# XMEGAbreakoutTH.net
KiCad netlist of a schematic drawn in EAGLE
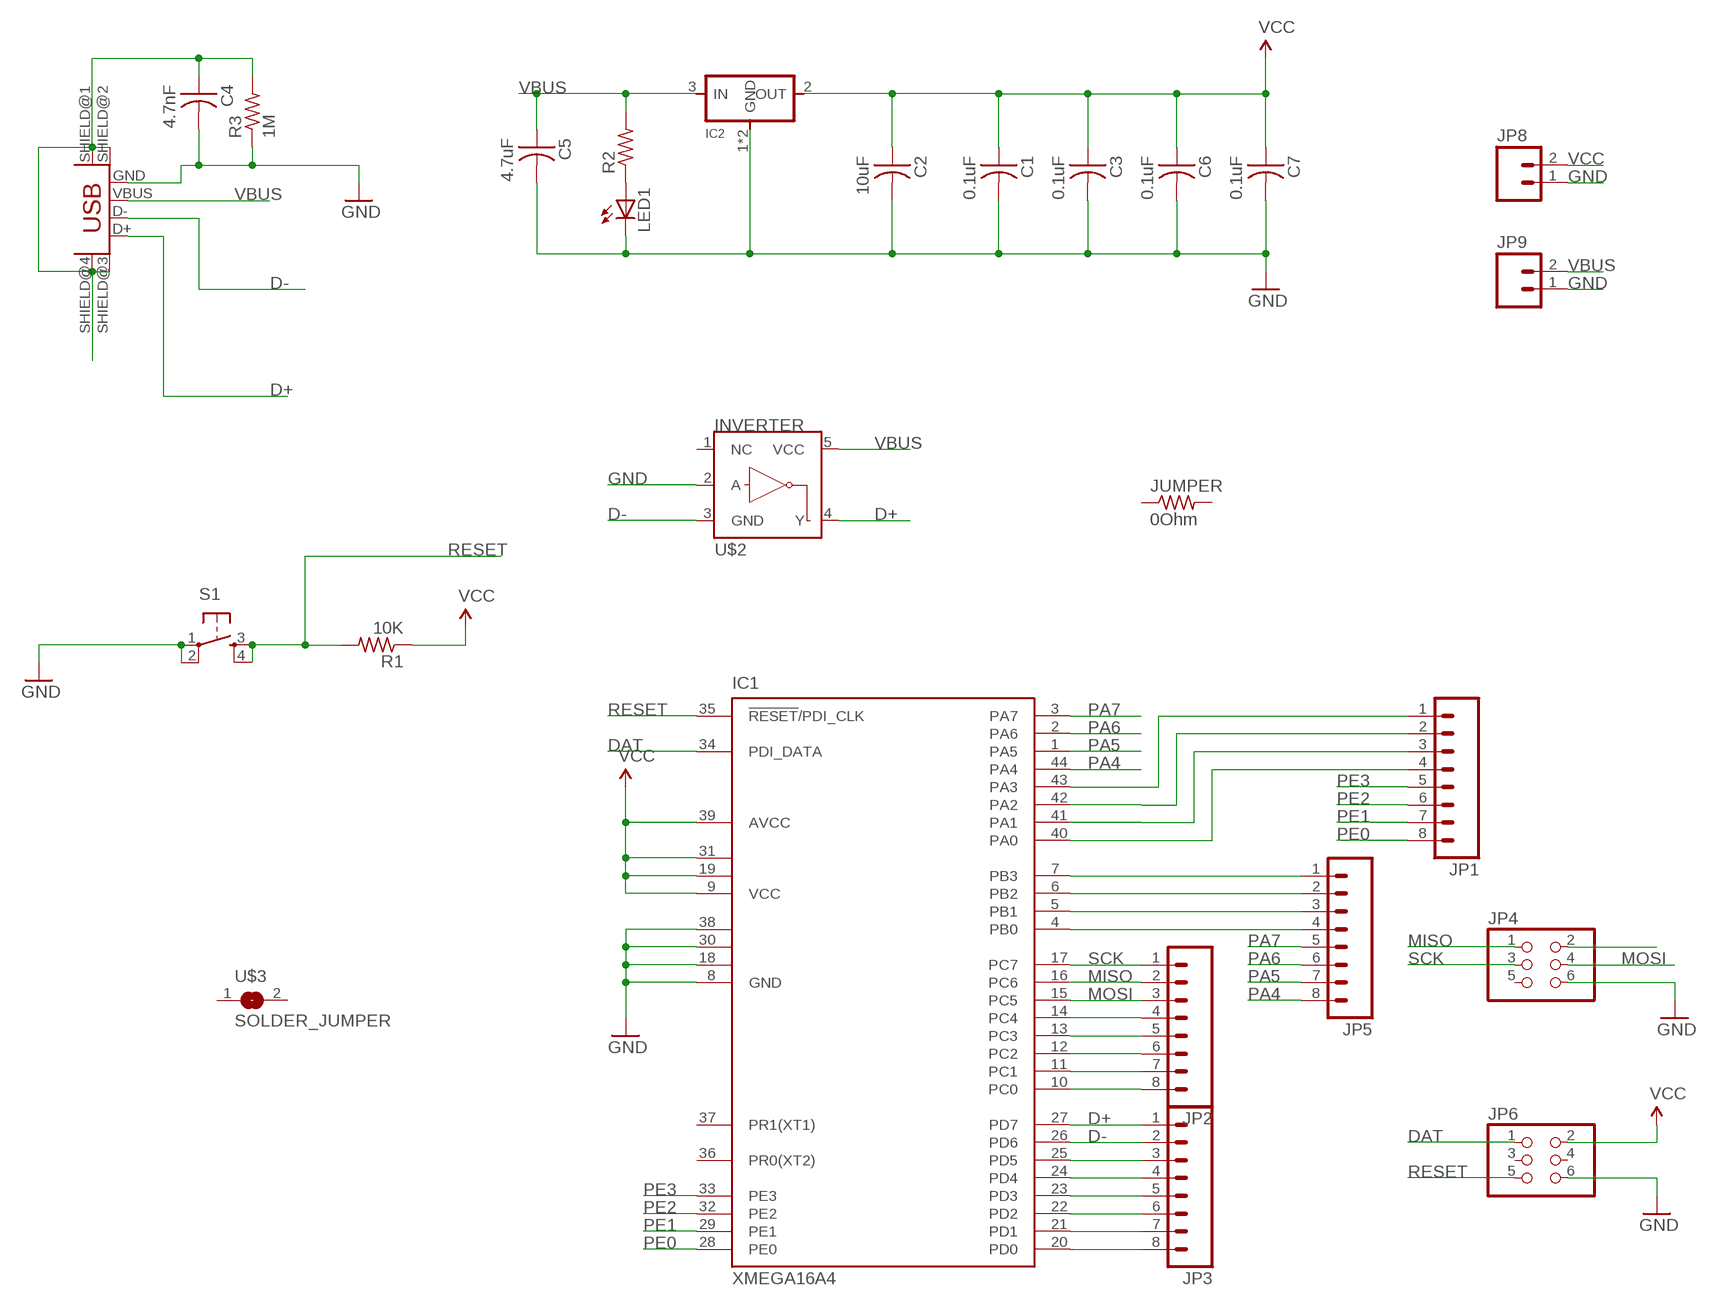
[diagram p0: schematic, sheet 1]

(export (version "E")
  (design (tool "Eeschema 10.0.6"))
  (components
    (comp (ref "C1")
      (value "0.1uF")
      (footprint "eagle-import:C1206")
      (libsource (lib "eagle-import") (part "CAP-US1206"))
    )
    (comp (ref "C2")
      (value "10uF")
      (footprint "eagle-import:C1206")
      (libsource (lib "eagle-import") (part "CAP-US1206"))
    )
    (comp (ref "C3")
      (value "0.1uF")
      (footprint "eagle-import:C1206FAB")
      (libsource (lib "eagle-import") (part "CAP-US1206FAB"))
    )
    (comp (ref "C4")
      (value "4.7nF")
      (footprint "eagle-import:C1206")
      (libsource (lib "eagle-import") (part "CAP-US1206"))
    )
    (comp (ref "C5")
      (value "4.7uF")
      (footprint "eagle-import:C1206")
      (libsource (lib "eagle-import") (part "CAP-US1206"))
    )
    (comp (ref "C6")
      (value "0.1uF")
      (footprint "eagle-import:C1206")
      (libsource (lib "eagle-import") (part "CAP-US1206"))
    )
    (comp (ref "C7")
      (value "0.1uF")
      (footprint "eagle-import:C1206")
      (libsource (lib "eagle-import") (part "CAP-US1206"))
    )
    (comp (ref "IC1")
      (value "XMEGA16A4")
      (footprint "eagle-import:TQFP44-FAB")
      (libsource (lib "eagle-import") (part "XMEGA16A4"))
    )
    (comp (ref "IC2")
      (value "REGULATORSOT223")
      (footprint "eagle-import:SOT223")
      (libsource (lib "eagle-import") (part "REGULATORSOT223"))
    )
    (comp (ref "JP1")
      (value "M081X08_2X1X4A")
      (footprint "eagle-import:1X08_2X1X4")
      (libsource (lib "eagle-import") (part "M081X08_2X1X4A"))
    )
    (comp (ref "JP2")
      (value "M081X08")
      (footprint "eagle-import:1X08")
      (libsource (lib "eagle-import") (part "M081X08"))
    )
    (comp (ref "JP3")
      (value "M081X08")
      (footprint "eagle-import:1X08")
      (libsource (lib "eagle-import") (part "M081X08"))
    )
    (comp (ref "JP4")
      (value "PINHD-2X3-SMD")
      (footprint "eagle-import:2X03SMD")
      (libsource (lib "eagle-import") (part "PINHD-2X3-SMD"))
    )
    (comp (ref "JP5")
      (value "M081X08")
      (footprint "eagle-import:1X08")
      (libsource (lib "eagle-import") (part "M081X08"))
    )
    (comp (ref "JP6")
      (value "PINHD-2X3-SMD")
      (footprint "eagle-import:2X03SMD")
      (libsource (lib "eagle-import") (part "PINHD-2X3-SMD"))
    )
    (comp (ref "JP8")
      (value "M02PTH")
      (footprint "eagle-import:1X02")
      (libsource (lib "eagle-import") (part "M02PTH"))
    )
    (comp (ref "JP9")
      (value "M02PTH")
      (footprint "eagle-import:1X02")
      (libsource (lib "eagle-import") (part "M02PTH"))
    )
    (comp (ref "JUMPER")
      (value "0Ohm")
      (footprint "eagle-import:R1206FAB")
      (libsource (lib "eagle-import") (part "RES-US1206FAB"))
    )
    (comp (ref "LED1")
      (value "LEDSMT1206")
      (footprint "eagle-import:1206")
      (libsource (lib "eagle-import") (part "LEDSMT1206"))
    )
    (comp (ref "R1")
      (value "10K")
      (footprint "eagle-import:R1206FAB")
      (libsource (lib "eagle-import") (part "RES-US1206FAB"))
    )
    (comp (ref "R2")
      (value "RES-US1206FAB")
      (footprint "eagle-import:R1206FAB")
      (libsource (lib "eagle-import") (part "RES-US1206FAB"))
    )
    (comp (ref "R3")
      (value "1M")
      (footprint "eagle-import:R1206FAB")
      (libsource (lib "eagle-import") (part "RES-US1206FAB"))
    )
    (comp (ref "S1")
      (value "6MM_SWITCH6MM_SWITCH")
      (footprint "eagle-import:6MM_SWITCH")
      (libsource (lib "eagle-import") (part "6MM_SWITCH6MM_SWITCH"))
    )
    (comp (ref "U$1")
      (value "USB_MINIB")
      (footprint "eagle-import:USB_MINIB")
      (libsource (lib "eagle-import") (part "USB_MINIB"))
    )
    (comp (ref "U$2")
      (value "INVERTER")
      (footprint "eagle-import:SOT23-5")
      (libsource (lib "eagle-import") (part "INVERTER"))
    )
    (comp (ref "U$3")
      (value "SOLDER_JUMPER")
      (footprint "eagle-import:SJFAB")
      (libsource (lib "eagle-import") (part "SOLDER_JUMPER"))
    )
  )
  (nets
    (net (code "1") (name "/D+") (class "Default")
      (node (ref "IC1") (pin "27") (pinfunction "PD7_27") (pintype "bidirectional"))
      (node (ref "JP3") (pin "1") (pinfunction "1_1") (pintype "passive"))
      (node (ref "U$1") (pin "D+") (pinfunction "D+_D+") (pintype "bidirectional"))
      (node (ref "U$2") (pin "4") (pinfunction "Y_4") (pintype "bidirectional"))
    )
    (net (code "2") (name "/D-") (class "Default")
      (node (ref "IC1") (pin "26") (pinfunction "PD6_26") (pintype "bidirectional"))
      (node (ref "JP3") (pin "2") (pinfunction "2_2") (pintype "passive"))
      (node (ref "U$1") (pin "D-") (pinfunction "D-_D-") (pintype "bidirectional"))
      (node (ref "U$2") (pin "3") (pinfunction "GND_3") (pintype "bidirectional"))
    )
    (net (code "3") (name "/DAT") (class "Default")
      (node (ref "IC1") (pin "34") (pinfunction "PDI_DATA_34") (pintype "bidirectional"))
      (node (ref "JP6") (pin "1") (pinfunction "1_1") (pintype "passive"))
    )
    (net (code "4") (name "/MISO") (class "Default")
      (node (ref "IC1") (pin "16") (pinfunction "PC6_16") (pintype "bidirectional"))
      (node (ref "JP2") (pin "2") (pinfunction "2_2") (pintype "passive"))
      (node (ref "JP4") (pin "1") (pinfunction "1_1") (pintype "passive"))
    )
    (net (code "5") (name "/MOSI") (class "Default")
      (node (ref "IC1") (pin "15") (pinfunction "PC5_15") (pintype "bidirectional"))
      (node (ref "JP2") (pin "3") (pinfunction "3_3") (pintype "passive"))
      (node (ref "JP4") (pin "4") (pinfunction "4_4") (pintype "passive"))
    )
    (net (code "6") (name "/PA4") (class "Default")
      (node (ref "IC1") (pin "44") (pinfunction "PA4_44") (pintype "bidirectional"))
      (node (ref "JP5") (pin "8") (pinfunction "8_8") (pintype "passive"))
    )
    (net (code "7") (name "/PA5") (class "Default")
      (node (ref "IC1") (pin "1") (pinfunction "PA5_1") (pintype "bidirectional"))
      (node (ref "JP5") (pin "7") (pinfunction "7_7") (pintype "passive"))
    )
    (net (code "8") (name "/PA6") (class "Default")
      (node (ref "IC1") (pin "2") (pinfunction "PA6_2") (pintype "bidirectional"))
      (node (ref "JP5") (pin "6") (pinfunction "6_6") (pintype "passive"))
    )
    (net (code "9") (name "/PA7") (class "Default")
      (node (ref "IC1") (pin "3") (pinfunction "PA7_3") (pintype "bidirectional"))
      (node (ref "JP5") (pin "5") (pinfunction "5_5") (pintype "passive"))
    )
    (net (code "10") (name "/PE0") (class "Default")
      (node (ref "IC1") (pin "28") (pinfunction "PE0_28") (pintype "bidirectional"))
      (node (ref "JP1") (pin "8") (pinfunction "8_8") (pintype "passive"))
    )
    (net (code "11") (name "/PE1") (class "Default")
      (node (ref "IC1") (pin "29") (pinfunction "PE1_29") (pintype "bidirectional"))
      (node (ref "JP1") (pin "7") (pinfunction "7_7") (pintype "passive"))
    )
    (net (code "12") (name "/PE2") (class "Default")
      (node (ref "IC1") (pin "32") (pinfunction "PE2_32") (pintype "bidirectional"))
      (node (ref "JP1") (pin "6") (pinfunction "6_6") (pintype "passive"))
    )
    (net (code "13") (name "/PE3") (class "Default")
      (node (ref "IC1") (pin "33") (pinfunction "PE3_33") (pintype "bidirectional"))
      (node (ref "JP1") (pin "5") (pinfunction "5_5") (pintype "passive"))
    )
    (net (code "14") (name "/RESET") (class "Default")
      (node (ref "IC1") (pin "35") (pinfunction "~{RESET}/PDI_CLK_35") (pintype "bidirectional"))
      (node (ref "JP6") (pin "5") (pinfunction "5_5") (pintype "passive"))
      (node (ref "R1") (pin "2") (pinfunction "2_2") (pintype "passive"))
      (node (ref "S1") (pin "3") (pinfunction "S_3") (pintype "passive"))
      (node (ref "S1") (pin "4") (pinfunction "S1_4") (pintype "passive"))
    )
    (net (code "15") (name "/SCK") (class "Default")
      (node (ref "IC1") (pin "17") (pinfunction "PC7_17") (pintype "bidirectional"))
      (node (ref "JP2") (pin "1") (pinfunction "1_1") (pintype "passive"))
      (node (ref "JP4") (pin "3") (pinfunction "3_3") (pintype "passive"))
    )
    (net (code "16") (name "/VBUS") (class "Default")
      (node (ref "C5") (pin "1") (pinfunction "1_1") (pintype "passive"))
      (node (ref "IC2") (pin "3") (pinfunction "IN_3") (pintype "bidirectional"))
      (node (ref "JP9") (pin "2") (pinfunction "2_2") (pintype "passive"))
      (node (ref "R2") (pin "2") (pinfunction "2_2") (pintype "passive"))
      (node (ref "U$1") (pin "VBUS") (pinfunction "VBUS_VBUS") (pintype "bidirectional"))
      (node (ref "U$2") (pin "5") (pinfunction "VCC_5") (pintype "bidirectional"))
    )
    (net (code "17") (name "GND") (class "Default")
      (node (ref "C1") (pin "2") (pinfunction "2_2") (pintype "passive"))
      (node (ref "C2") (pin "2") (pinfunction "2_2") (pintype "passive"))
      (node (ref "C3") (pin "2") (pinfunction "2_2") (pintype "passive"))
      (node (ref "C4") (pin "2") (pinfunction "2_2") (pintype "passive"))
      (node (ref "C5") (pin "2") (pinfunction "2_2") (pintype "passive"))
      (node (ref "C6") (pin "2") (pinfunction "2_2") (pintype "passive"))
      (node (ref "C7") (pin "2") (pinfunction "2_2") (pintype "passive"))
      (node (ref "IC1") (pin "18") (pinfunction "GND1_18") (pintype "power_in"))
      (node (ref "IC1") (pin "30") (pinfunction "GND2_30") (pintype "power_in"))
      (node (ref "IC1") (pin "38") (pinfunction "GND3_38") (pintype "power_in"))
      (node (ref "IC1") (pin "8") (pinfunction "GND_8") (pintype "power_in"))
      (node (ref "IC2") (pin "1") (pinfunction "GND_1") (pintype "bidirectional"))
      (node (ref "IC2") (pin "4") (pinfunction "GND_4") (pintype "bidirectional"))
      (node (ref "JP4") (pin "6") (pinfunction "6_6") (pintype "passive"))
      (node (ref "JP6") (pin "6") (pinfunction "6_6") (pintype "passive"))
      (node (ref "JP8") (pin "1") (pinfunction "1_1") (pintype "passive"))
      (node (ref "JP9") (pin "1") (pinfunction "1_1") (pintype "passive"))
      (node (ref "LED1") (pin "C") (pinfunction "C_C") (pintype "passive"))
      (node (ref "R3") (pin "1") (pinfunction "1_1") (pintype "passive"))
      (node (ref "S1") (pin "1") (pinfunction "P_1") (pintype "passive"))
      (node (ref "S1") (pin "2") (pinfunction "P1_2") (pintype "passive"))
      (node (ref "U$1") (pin "GND") (pinfunction "GND_GND") (pintype "bidirectional"))
      (node (ref "U$2") (pin "2") (pinfunction "A_2") (pintype "bidirectional"))
    )
    (net (code "18") (name "Net-(IC1-PA0)") (class "Default")
      (node (ref "IC1") (pin "40") (pinfunction "PA0_40") (pintype "bidirectional"))
      (node (ref "JP1") (pin "4") (pinfunction "4_4") (pintype "passive"))
    )
    (net (code "19") (name "Net-(IC1-PA1)") (class "Default")
      (node (ref "IC1") (pin "41") (pinfunction "PA1_41") (pintype "bidirectional"))
      (node (ref "JP1") (pin "3") (pinfunction "3_3") (pintype "passive"))
    )
    (net (code "20") (name "Net-(IC1-PA2)") (class "Default")
      (node (ref "IC1") (pin "42") (pinfunction "PA2_42") (pintype "bidirectional"))
      (node (ref "JP1") (pin "2") (pinfunction "2_2") (pintype "passive"))
    )
    (net (code "21") (name "Net-(IC1-PA3)") (class "Default")
      (node (ref "IC1") (pin "43") (pinfunction "PA3_43") (pintype "bidirectional"))
      (node (ref "JP1") (pin "1") (pinfunction "1_1") (pintype "passive"))
    )
    (net (code "22") (name "Net-(IC1-PB0)") (class "Default")
      (node (ref "IC1") (pin "4") (pinfunction "PB0_4") (pintype "bidirectional"))
      (node (ref "JP5") (pin "4") (pinfunction "4_4") (pintype "passive"))
    )
    (net (code "23") (name "Net-(IC1-PB1)") (class "Default")
      (node (ref "IC1") (pin "5") (pinfunction "PB1_5") (pintype "bidirectional"))
      (node (ref "JP5") (pin "3") (pinfunction "3_3") (pintype "passive"))
    )
    (net (code "24") (name "Net-(IC1-PB2)") (class "Default")
      (node (ref "IC1") (pin "6") (pinfunction "PB2_6") (pintype "bidirectional"))
      (node (ref "JP5") (pin "2") (pinfunction "2_2") (pintype "passive"))
    )
    (net (code "25") (name "Net-(IC1-PB3)") (class "Default")
      (node (ref "IC1") (pin "7") (pinfunction "PB3_7") (pintype "bidirectional"))
      (node (ref "JP5") (pin "1") (pinfunction "1_1") (pintype "passive"))
    )
    (net (code "26") (name "Net-(IC1-PC0)") (class "Default")
      (node (ref "IC1") (pin "10") (pinfunction "PC0_10") (pintype "bidirectional"))
      (node (ref "JP2") (pin "8") (pinfunction "8_8") (pintype "passive"))
    )
    (net (code "27") (name "Net-(IC1-PC1)") (class "Default")
      (node (ref "IC1") (pin "11") (pinfunction "PC1_11") (pintype "bidirectional"))
      (node (ref "JP2") (pin "7") (pinfunction "7_7") (pintype "passive"))
    )
    (net (code "28") (name "Net-(IC1-PC2)") (class "Default")
      (node (ref "IC1") (pin "12") (pinfunction "PC2_12") (pintype "bidirectional"))
      (node (ref "JP2") (pin "6") (pinfunction "6_6") (pintype "passive"))
    )
    (net (code "29") (name "Net-(IC1-PC3)") (class "Default")
      (node (ref "IC1") (pin "13") (pinfunction "PC3_13") (pintype "bidirectional"))
      (node (ref "JP2") (pin "5") (pinfunction "5_5") (pintype "passive"))
    )
    (net (code "30") (name "Net-(IC1-PC4)") (class "Default")
      (node (ref "IC1") (pin "14") (pinfunction "PC4_14") (pintype "bidirectional"))
      (node (ref "JP2") (pin "4") (pinfunction "4_4") (pintype "passive"))
    )
    (net (code "31") (name "Net-(IC1-PD0)") (class "Default")
      (node (ref "IC1") (pin "20") (pinfunction "PD0_20") (pintype "bidirectional"))
      (node (ref "JP3") (pin "8") (pinfunction "8_8") (pintype "passive"))
    )
    (net (code "32") (name "Net-(IC1-PD1)") (class "Default")
      (node (ref "IC1") (pin "21") (pinfunction "PD1_21") (pintype "bidirectional"))
      (node (ref "JP3") (pin "7") (pinfunction "7_7") (pintype "passive"))
    )
    (net (code "33") (name "Net-(IC1-PD2)") (class "Default")
      (node (ref "IC1") (pin "22") (pinfunction "PD2_22") (pintype "bidirectional"))
      (node (ref "JP3") (pin "6") (pinfunction "6_6") (pintype "passive"))
    )
    (net (code "34") (name "Net-(IC1-PD3)") (class "Default")
      (node (ref "IC1") (pin "23") (pinfunction "PD3_23") (pintype "bidirectional"))
      (node (ref "JP3") (pin "5") (pinfunction "5_5") (pintype "passive"))
    )
    (net (code "35") (name "Net-(IC1-PD4)") (class "Default")
      (node (ref "IC1") (pin "24") (pinfunction "PD4_24") (pintype "bidirectional"))
      (node (ref "JP3") (pin "4") (pinfunction "4_4") (pintype "passive"))
    )
    (net (code "36") (name "Net-(IC1-PD5)") (class "Default")
      (node (ref "IC1") (pin "25") (pinfunction "PD5_25") (pintype "bidirectional"))
      (node (ref "JP3") (pin "3") (pinfunction "3_3") (pintype "passive"))
    )
    (net (code "37") (name "Net-(LED1-PadA)") (class "Default")
      (node (ref "LED1") (pin "A") (pinfunction "A_A") (pintype "passive"))
      (node (ref "R2") (pin "1") (pinfunction "1_1") (pintype "passive"))
    )
    (net (code "38") (name "Net-(U$1-SHIELD)") (class "Default")
      (node (ref "C4") (pin "1") (pinfunction "1_1") (pintype "passive"))
      (node (ref "R3") (pin "2") (pinfunction "2_2") (pintype "passive"))
      (node (ref "U$1") (pin "SHIELD@1") (pinfunction "SHIELD_SHIELD@1") (pintype "passive"))
      (node (ref "U$1") (pin "SHIELD@2") (pinfunction "SHIELD1_SHIELD@2") (pintype "passive"))
      (node (ref "U$1") (pin "SHIELD@3") (pinfunction "SHIELD2_SHIELD@3") (pintype "passive"))
      (node (ref "U$1") (pin "SHIELD@4") (pinfunction "SHIELD3_SHIELD@4") (pintype "passive"))
    )
    (net (code "39") (name "VCC") (class "Default")
      (node (ref "C1") (pin "1") (pinfunction "1_1") (pintype "passive"))
      (node (ref "C2") (pin "1") (pinfunction "1_1") (pintype "passive"))
      (node (ref "C3") (pin "1") (pinfunction "1_1") (pintype "passive"))
      (node (ref "C6") (pin "1") (pinfunction "1_1") (pintype "passive"))
      (node (ref "C7") (pin "1") (pinfunction "1_1") (pintype "passive"))
      (node (ref "IC1") (pin "19") (pinfunction "VCC1_19") (pintype "power_in"))
      (node (ref "IC1") (pin "31") (pinfunction "VCC2_31") (pintype "power_in"))
      (node (ref "IC1") (pin "39") (pinfunction "AVCC_39") (pintype "power_in"))
      (node (ref "IC1") (pin "9") (pinfunction "VCC_9") (pintype "power_in"))
      (node (ref "IC2") (pin "2") (pinfunction "OUT_2") (pintype "bidirectional"))
      (node (ref "JP6") (pin "2") (pinfunction "2_2") (pintype "passive"))
      (node (ref "JP8") (pin "2") (pinfunction "2_2") (pintype "passive"))
      (node (ref "R1") (pin "1") (pinfunction "1_1") (pintype "passive"))
    )
    (net (code "40") (name "unconnected-(IC1-PR0(XT2)-Pad36)") (class "Default")
      (node (ref "IC1") (pin "36") (pinfunction "PR0(XT2)_36") (pintype "bidirectional"))
    )
    (net (code "41") (name "unconnected-(IC1-PR1(XT1)-Pad37)") (class "Default")
      (node (ref "IC1") (pin "37") (pinfunction "PR1(XT1)_37") (pintype "bidirectional"))
    )
    (net (code "42") (name "unconnected-(JP4-Pad2)") (class "Default")
      (node (ref "JP4") (pin "2") (pinfunction "2_2") (pintype "passive"))
    )
    (net (code "43") (name "unconnected-(JP4-Pad5)") (class "Default")
      (node (ref "JP4") (pin "5") (pinfunction "5_5") (pintype "passive"))
    )
    (net (code "44") (name "unconnected-(JP6-Pad3)") (class "Default")
      (node (ref "JP6") (pin "3") (pinfunction "3_3") (pintype "passive"))
    )
    (net (code "45") (name "unconnected-(JP6-Pad4)") (class "Default")
      (node (ref "JP6") (pin "4") (pinfunction "4_4") (pintype "passive"))
    )
    (net (code "46") (name "unconnected-(JUMPER-Pad1)") (class "Default")
      (node (ref "JUMPER") (pin "1") (pinfunction "1_1") (pintype "passive"))
    )
    (net (code "47") (name "unconnected-(JUMPER-Pad2)") (class "Default")
      (node (ref "JUMPER") (pin "2") (pinfunction "2_2") (pintype "passive"))
    )
    (net (code "48") (name "unconnected-(U$2-NC-Pad1)") (class "Default")
      (node (ref "U$2") (pin "1") (pinfunction "NC_1") (pintype "bidirectional"))
    )
    (net (code "49") (name "unconnected-(U$3-Pad1)") (class "Default")
      (node (ref "U$3") (pin "1") (pinfunction "1_1") (pintype "passive"))
    )
    (net (code "50") (name "unconnected-(U$3-Pad2)") (class "Default")
      (node (ref "U$3") (pin "2") (pinfunction "2_2") (pintype "passive"))
    )
  )
)
